# STM32F407.net
KiCad netlist of a schematic drawn in Altium Designer
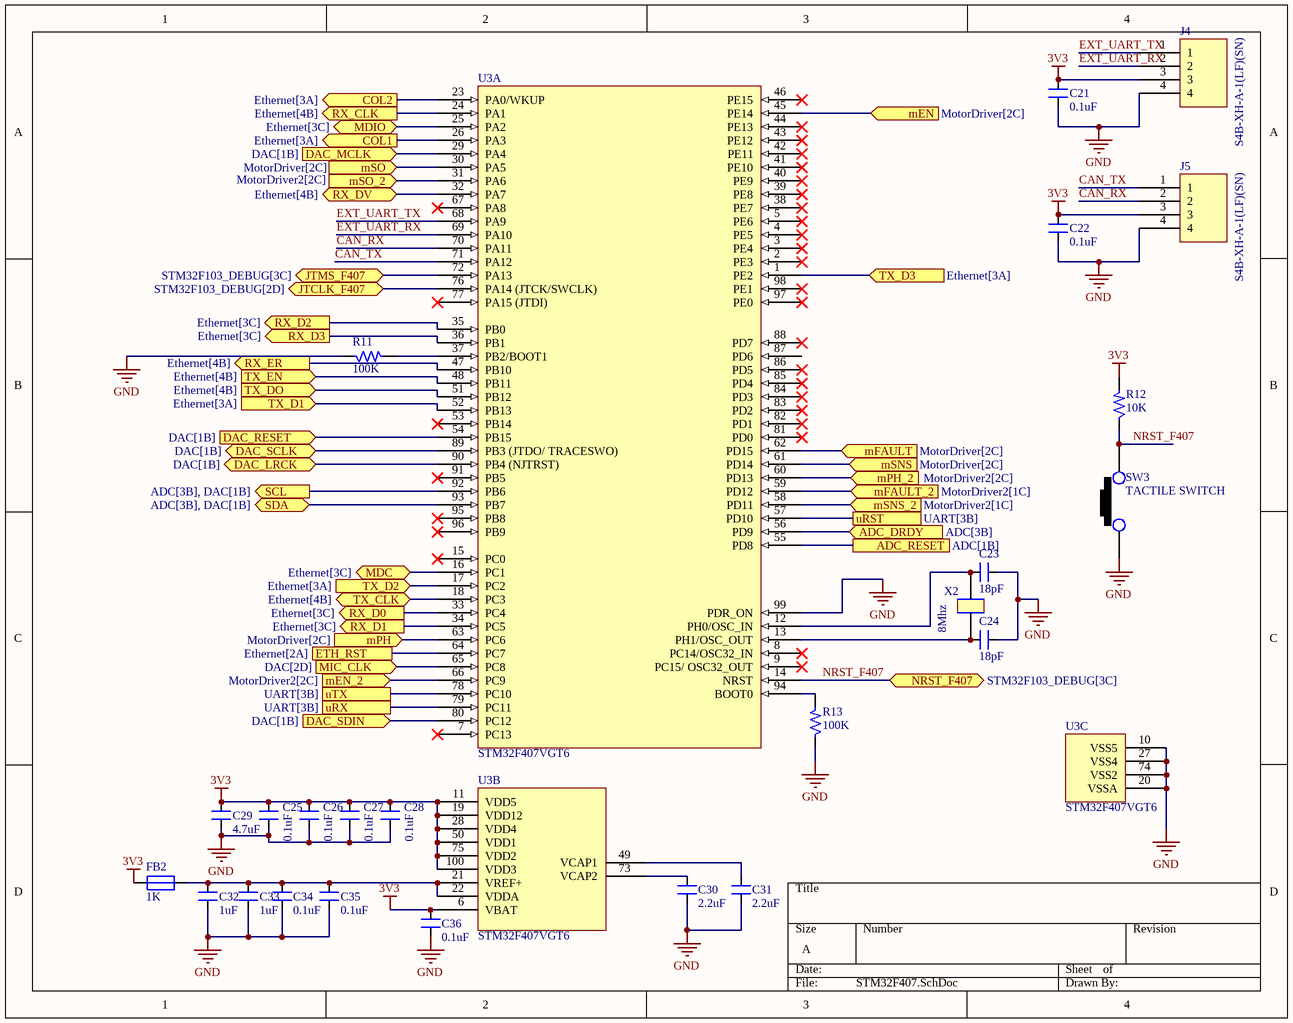
[diagram p0: STM32F407.SchDoc]

(export (version "E")
  (design (tool "Eeschema 10.0.6"))
  (components
    (comp (ref "C21")
      (value "0.1uF")
      (footprint "CAP_0805")
      (description "0.1µF ±5% 50V Ceramic Capacitor X7R 0805 (2012 Metric)")
      (fields
        (field (name "MANUFACTURER") "AVX Corporation")
        (field (name "MANUFACTURER PART NUMBER") "08055C104JAT4A")
      )
      (libsource (lib "ESTEEMPCBLIB") (part "CAP_0.1uF-50V-5%-0805"))
    )
    (comp (ref "C22")
      (value "0.1uF")
      (footprint "CAP_0805")
      (description "0.1µF ±5% 50V Ceramic Capacitor X7R 0805 (2012 Metric)")
      (fields
        (field (name "MANUFACTURER") "AVX Corporation")
        (field (name "MANUFACTURER PART NUMBER") "08055C104JAT4A")
      )
      (libsource (lib "ESTEEMPCBLIB") (part "CAP_0.1uF-50V-5%-0805"))
    )
    (comp (ref "C23")
      (value "18pF")
      (footprint "CAP_0805")
      (description "18pF ±5% 50V Ceramic Capacitor C0G, NP0 0805 (2012 Metric)")
      (fields
        (field (name "MANUFACTURER") "Yageo")
        (field (name "MANUFACTURER PART NUMBER") "CL21C180JBANNNC")
      )
      (libsource (lib "ESTEEMPCBLIB") (part "CAP_18pF-50V-5%-0805"))
    )
    (comp (ref "C24")
      (value "18pF")
      (footprint "CAP_0805")
      (description "18pF ±5% 50V Ceramic Capacitor C0G, NP0 0805 (2012 Metric)")
      (fields
        (field (name "MANUFACTURER") "Yageo")
        (field (name "MANUFACTURER PART NUMBER") "CL21C180JBANNNC")
      )
      (libsource (lib "ESTEEMPCBLIB") (part "CAP_18pF-50V-5%-0805"))
    )
    (comp (ref "C25")
      (value "0.1uF")
      (footprint "CAP_0805")
      (description "0.1µF ±5% 50V Ceramic Capacitor X7R 0805 (2012 Metric)")
      (fields
        (field (name "MANUFACTURER") "AVX Corporation")
        (field (name "MANUFACTURER PART NUMBER") "08055C104JAT4A")
      )
      (libsource (lib "ESTEEMPCBLIB") (part "CAP_0.1uF-50V-5%-0805"))
    )
    (comp (ref "C26")
      (value "0.1uF")
      (footprint "CAP_0805")
      (description "0.1µF ±5% 50V Ceramic Capacitor X7R 0805 (2012 Metric)")
      (fields
        (field (name "MANUFACTURER") "AVX Corporation")
        (field (name "MANUFACTURER PART NUMBER") "08055C104JAT4A")
      )
      (libsource (lib "ESTEEMPCBLIB") (part "CAP_0.1uF-50V-5%-0805"))
    )
    (comp (ref "C27")
      (value "0.1uF")
      (footprint "CAP_0805")
      (description "0.1µF ±5% 50V Ceramic Capacitor X7R 0805 (2012 Metric)")
      (fields
        (field (name "MANUFACTURER") "AVX Corporation")
        (field (name "MANUFACTURER PART NUMBER") "08055C104JAT4A")
      )
      (libsource (lib "ESTEEMPCBLIB") (part "CAP_0.1uF-50V-5%-0805"))
    )
    (comp (ref "C28")
      (value "0.1uF")
      (footprint "CAP_0805")
      (description "0.1µF ±5% 50V Ceramic Capacitor X7R 0805 (2012 Metric)")
      (fields
        (field (name "MANUFACTURER") "AVX Corporation")
        (field (name "MANUFACTURER PART NUMBER") "08055C104JAT4A")
      )
      (libsource (lib "ESTEEMPCBLIB") (part "CAP_0.1uF-50V-5%-0805"))
    )
    (comp (ref "C29")
      (value "4.7uF")
      (footprint "CAP_0805")
      (description "4.7µF ±10% 50V Ceramic Capacitor X5R 0805 (2012 Metric)")
      (fields
        (field (name "MANUFACTURER") "Yageo")
        (field (name "MANUFACTURER PART NUMBER") "GRM21BR61H475KE51L")
      )
      (libsource (lib "ESTEEMPCBLIB") (part "CAP_4.7uF-50V-10%-0805"))
    )
    (comp (ref "C30")
      (value "2.2uF")
      (footprint "CAP_0805")
      (description "2.2µF ±10% 25V Ceramic Capacitor X7R 0805 (2012 Metric)")
      (fields
        (field (name "MANUFACTURER") "KEMET")
        (field (name "MANUFACTURER PART NUMBER") "CL21B225KAFNFNE")
      )
      (libsource (lib "ESTEEMPCBLIB") (part "CAP_2.2uF-25V-10%-0805"))
    )
    (comp (ref "C31")
      (value "2.2uF")
      (footprint "CAP_0805")
      (description "2.2µF ±10% 25V Ceramic Capacitor X7R 0805 (2012 Metric)")
      (fields
        (field (name "MANUFACTURER") "KEMET")
        (field (name "MANUFACTURER PART NUMBER") "CL21B225KAFNFNE")
      )
      (libsource (lib "ESTEEMPCBLIB") (part "CAP_2.2uF-25V-10%-0805"))
    )
    (comp (ref "C32")
      (value "1uF")
      (footprint "CAP_0805")
      (description "1µF ±5% 50V Ceramic Capacitor X7R 0805 (2012 Metric)")
      (fields
        (field (name "MANUFACTURER") "Samsung")
        (field (name "MANUFACTURER PART NUMBER") "CC0805JKX7R9BB105")
      )
      (libsource (lib "ESTEEMPCBLIB") (part "CAP_1uF-50V-5%-0805"))
    )
    (comp (ref "C33")
      (value "1uF")
      (footprint "CAP_0805")
      (description "1µF ±5% 50V Ceramic Capacitor X7R 0805 (2012 Metric)")
      (fields
        (field (name "MANUFACTURER") "Samsung")
        (field (name "MANUFACTURER PART NUMBER") "CC0805JKX7R9BB105")
      )
      (libsource (lib "ESTEEMPCBLIB") (part "CAP_1uF-50V-5%-0805"))
    )
    (comp (ref "C34")
      (value "0.1uF")
      (footprint "CAP_0805")
      (description "0.1µF ±5% 50V Ceramic Capacitor X7R 0805 (2012 Metric)")
      (fields
        (field (name "MANUFACTURER") "AVX Corporation")
        (field (name "MANUFACTURER PART NUMBER") "08055C104JAT4A")
      )
      (libsource (lib "ESTEEMPCBLIB") (part "CAP_0.1uF-50V-5%-0805"))
    )
    (comp (ref "C35")
      (value "0.1uF")
      (footprint "CAP_0805")
      (description "0.1µF ±5% 50V Ceramic Capacitor X7R 0805 (2012 Metric)")
      (fields
        (field (name "MANUFACTURER") "AVX Corporation")
        (field (name "MANUFACTURER PART NUMBER") "08055C104JAT4A")
      )
      (libsource (lib "ESTEEMPCBLIB") (part "CAP_0.1uF-50V-5%-0805"))
    )
    (comp (ref "C36")
      (value "0.1uF")
      (footprint "CAP_0805")
      (description "0.1µF ±5% 50V Ceramic Capacitor X7R 0805 (2012 Metric)")
      (fields
        (field (name "MANUFACTURER") "AVX Corporation")
        (field (name "MANUFACTURER PART NUMBER") "08055C104JAT4A")
      )
      (libsource (lib "ESTEEMPCBLIB") (part "CAP_0.1uF-50V-5%-0805"))
    )
    (comp (ref "FB2")
      (value "1K")
      (footprint "IND_0805")
      (description "1 kOhms @ 100MHz 1 Power Line Ferrite Bead 0805 (2012 Metric) 1.6A")
      (fields
        (field (name "MANUFACTURER") "Laird")
        (field (name "MANUFACTURER PART NUMBER") "BLM21SP102SH1D")
      )
      (libsource (lib "ESTEEMPCBLIB") (part "FB_1K-100MHZ-1.6A-0805"))
    )
    (comp (ref "J4")
      (value "S4B-XH-A-1(LF)(SN)")
      (footprint "CON4_100_S4B-XH-A_TH_RA")
      (description "4 Pins, 1 Row 2.54mm Pitch, right angle Connector, male")
      (fields (field (name "MANUFACTURER") "Wurth Electronics") (field (name "MATING PART NUMBER") "XHP-4"))
      (libsource (lib "ESTEEMPCBLIB") (part "CON-PLG_4X1-100-RA-TH"))
    )
    (comp (ref "J5")
      (value "S4B-XH-A-1(LF)(SN)")
      (footprint "CON4_100_S4B-XH-A_TH_RA")
      (description "4 Pins, 1 Row 2.54mm Pitch, right angle Connector, male")
      (fields (field (name "MANUFACTURER") "Wurth Electronics") (field (name "MATING PART NUMBER") "XHP-4"))
      (libsource (lib "ESTEEMPCBLIB") (part "CON-PLG_4X1-100-RA-TH"))
    )
    (comp (ref "R11")
      (value "100K")
      (footprint "RES_0805")
      (description "100 kOhms ±1% 0.125W, 1/8W Chip Resistor 0805 (2012 Metric) Automotive AEC-Q200 Thick Film")
      (fields (field (name "MANUFACTURER") "Walsin") (field (name "MANUFACTURER PART NUMBER") "WR08X1003FTL"))
      (libsource (lib "ESTEEMPCBLIB") (part "RES_100K-0.125W-1%-0805"))
    )
    (comp (ref "R12")
      (value "10K")
      (footprint "RES_0603")
      (description "10 kOhms ±1% 0.1W, 1/10W Chip Resistor 0603 (1608 Metric) Automotive AEC-Q200 Thick Film")
      (fields (field (name "MANUFACTURER") "Walsin") (field (name "MANUFACTURER PART NUMBER") "WR06X1002FTL"))
      (libsource (lib "ESTEEMPCBLIB") (part "RES_10K-0.1W-1%-0603"))
    )
    (comp (ref "R13")
      (value "100K")
      (footprint "RES_0805")
      (description "100 kOhms ±1% 0.125W, 1/8W Chip Resistor 0805 (2012 Metric) Automotive AEC-Q200 Thick Film")
      (fields (field (name "MANUFACTURER") "Walsin") (field (name "MANUFACTURER PART NUMBER") "WR08X1003FTL"))
      (libsource (lib "ESTEEMPCBLIB") (part "RES_100K-0.125W-1%-0805"))
    )
    (comp (ref "SW3")
      (value "TACTILE SWITCH")
      (footprint "SW_342_SMD")
      (description "Tactile Switch SPST-NO Top Actuated Surface Mount")
      (fields
        (field (name "MANUFACTURER") "ITT C&K")
        (field (name "MANUFACTURER PART NUMBER") "RS-282G05A3-SMRT")
      )
      (libsource (lib "ESTEEMPCBLIB") (part "SW1_RS-282G05A3-SMRT-SMD"))
    )
    (comp (ref "U3")
      (value "STM32F407VGT6")
      (footprint "QFN100_19.6_669_58X10_SMD")
      (description "ARM® Cortex®-M4 STM32F4 Microcontroller IC 32-Bit 168MHz 1MB (1M x 8) FLASH 100-LQFP (14x14)")
      (fields (field (name "MANUFACTURER") "STMicroelectronics"))
      (libsource (lib "ESTEEMPCBLIB") (part "IC_STM32F407VGT6"))
    )
    (comp (ref "X2")
      (value "8Mhz")
      (footprint "XTAL_314_240X47_SMD")
      (description "8MHz ±30ppm Crystal 32pF 60 Ohms HC-49/US")
      (fields
        (field (name "MANUFACTURER") "Fox Electronics")
        (field (name "MANUFACTURER PART NUMBER") "ECS-80-32-5PX-TR")
      )
      (libsource (lib "ESTEEMPCBLIB") (part "XTAL_8MHZ-ECS-80-32-5PX-SMD"))
    )
  )
  (nets
    (net (code "1") (name "/ADC_DRDY") (class "Default")
      (node (ref "U3") (pin "56") (pinfunction "PD9_56") (pintype "input"))
    )
    (net (code "2") (name "/ADC_RESET") (class "Default")
      (node (ref "U3") (pin "55") (pinfunction "PD8_55") (pintype "input"))
    )
    (net (code "3") (name "/CAN_RX") (class "Default")
      (node (ref "J5") (pin "2") (pinfunction "2_2") (pintype "passive"))
      (node (ref "U3") (pin "70") (pinfunction "PA11_70") (pintype "input"))
    )
    (net (code "4") (name "/CAN_TX") (class "Default")
      (node (ref "J5") (pin "1") (pinfunction "1_1") (pintype "passive"))
      (node (ref "U3") (pin "71") (pinfunction "PA12_71") (pintype "input"))
    )
    (net (code "5") (name "/COL1") (class "Default")
      (node (ref "U3") (pin "26") (pinfunction "PA3_26") (pintype "input"))
    )
    (net (code "6") (name "/COL2") (class "Default")
      (node (ref "U3") (pin "23") (pinfunction "PA0/WKUP_23") (pintype "input"))
    )
    (net (code "7") (name "/DAC_LRCK") (class "Default")
      (node (ref "U3") (pin "90") (pinfunction "PB4_(NJTRST)_90") (pintype "input"))
    )
    (net (code "8") (name "/DAC_MCLK") (class "Default")
      (node (ref "U3") (pin "29") (pinfunction "PA4_29") (pintype "input"))
    )
    (net (code "9") (name "/DAC_RESET") (class "Default")
      (node (ref "U3") (pin "54") (pinfunction "PB15_54") (pintype "input"))
    )
    (net (code "10") (name "/DAC_SCLK") (class "Default")
      (node (ref "U3") (pin "89") (pinfunction "PB3_(JTDO/_TRACESWO)_89") (pintype "input"))
    )
    (net (code "11") (name "/DAC_SDIN") (class "Default")
      (node (ref "U3") (pin "80") (pinfunction "PC12_80") (pintype "input"))
    )
    (net (code "12") (name "/ETH_RST") (class "Default")
      (node (ref "U3") (pin "64") (pinfunction "PC7_64") (pintype "input"))
    )
    (net (code "13") (name "/EXT_UART_RX") (class "Default")
      (node (ref "J4") (pin "2") (pinfunction "2_2") (pintype "passive"))
      (node (ref "U3") (pin "69") (pinfunction "PA10_69") (pintype "input"))
    )
    (net (code "14") (name "/EXT_UART_TX") (class "Default")
      (node (ref "J4") (pin "1") (pinfunction "1_1") (pintype "passive"))
      (node (ref "U3") (pin "68") (pinfunction "PA9_68") (pintype "input"))
    )
    (net (code "15") (name "/JTCLK_F407") (class "Default")
      (node (ref "U3") (pin "76") (pinfunction "PA14_(JTCK/SWCLK)_76") (pintype "input"))
    )
    (net (code "16") (name "/JTMS_F407") (class "Default")
      (node (ref "U3") (pin "72") (pinfunction "PA13_72") (pintype "input"))
    )
    (net (code "17") (name "/MDC") (class "Default")
      (node (ref "U3") (pin "16") (pinfunction "PC1_16") (pintype "input"))
    )
    (net (code "18") (name "/MDIO") (class "Default")
      (node (ref "U3") (pin "25") (pinfunction "PA2_25") (pintype "input"))
    )
    (net (code "19") (name "/MIC_CLK") (class "Default")
      (node (ref "U3") (pin "65") (pinfunction "PC8_65") (pintype "input"))
    )
    (net (code "20") (name "/NRST_F407") (class "Default")
      (node (ref "R12") (pin "1") (pinfunction "1_1") (pintype "passive"))
      (node (ref "SW3") (pin "2") (pinfunction "2_2") (pintype "passive"))
      (node (ref "U3") (pin "14") (pinfunction "NRST_14") (pintype "input"))
    )
    (net (code "21") (name "/RX_CLK") (class "Default")
      (node (ref "U3") (pin "24") (pinfunction "PA1_24") (pintype "input"))
    )
    (net (code "22") (name "/RX_D0") (class "Default")
      (node (ref "U3") (pin "33") (pinfunction "PC4_33") (pintype "input"))
    )
    (net (code "23") (name "/RX_D1") (class "Default")
      (node (ref "U3") (pin "34") (pinfunction "PC5_34") (pintype "input"))
    )
    (net (code "24") (name "/RX_D2") (class "Default")
      (node (ref "U3") (pin "35") (pinfunction "PB0_35") (pintype "input"))
    )
    (net (code "25") (name "/RX_D3") (class "Default")
      (node (ref "U3") (pin "36") (pinfunction "PB1_36") (pintype "input"))
    )
    (net (code "26") (name "/RX_DV") (class "Default")
      (node (ref "U3") (pin "32") (pinfunction "PA7_32") (pintype "input"))
    )
    (net (code "27") (name "/RX_ER") (class "Default")
      (node (ref "U3") (pin "47") (pinfunction "PB10_47") (pintype "input"))
    )
    (net (code "28") (name "/SCL") (class "Default")
      (node (ref "U3") (pin "92") (pinfunction "PB6_92") (pintype "input"))
    )
    (net (code "29") (name "/SDA") (class "Default")
      (node (ref "U3") (pin "93") (pinfunction "PB7_93") (pintype "input"))
    )
    (net (code "30") (name "/TX_CLK") (class "Default")
      (node (ref "U3") (pin "18") (pinfunction "PC3_18") (pintype "input"))
    )
    (net (code "31") (name "/TX_D1") (class "Default")
      (node (ref "U3") (pin "52") (pinfunction "PB13_52") (pintype "input"))
    )
    (net (code "32") (name "/TX_D2") (class "Default")
      (node (ref "U3") (pin "17") (pinfunction "PC2_17") (pintype "input"))
    )
    (net (code "33") (name "/TX_D3") (class "Default")
      (node (ref "U3") (pin "1") (pinfunction "PE2_1") (pintype "input"))
    )
    (net (code "34") (name "/TX_DO") (class "Default")
      (node (ref "U3") (pin "51") (pinfunction "PB12_51") (pintype "input"))
    )
    (net (code "35") (name "/TX_EN") (class "Default")
      (node (ref "U3") (pin "48") (pinfunction "PB11_48") (pintype "input"))
    )
    (net (code "36") (name "/mEN") (class "Default")
      (node (ref "U3") (pin "45") (pinfunction "PE14_45") (pintype "input"))
    )
    (net (code "37") (name "/mEN_2") (class "Default")
      (node (ref "U3") (pin "66") (pinfunction "PC9_66") (pintype "input"))
    )
    (net (code "38") (name "/mFAULT") (class "Default")
      (node (ref "U3") (pin "62") (pinfunction "PD15_62") (pintype "input"))
    )
    (net (code "39") (name "/mFAULT_2") (class "Default")
      (node (ref "U3") (pin "59") (pinfunction "PD12_59") (pintype "input"))
    )
    (net (code "40") (name "/mPH") (class "Default")
      (node (ref "U3") (pin "63") (pinfunction "PC6_63") (pintype "input"))
    )
    (net (code "41") (name "/mPH_2") (class "Default")
      (node (ref "U3") (pin "60") (pinfunction "PD13_60") (pintype "input"))
    )
    (net (code "42") (name "/mSNS") (class "Default")
      (node (ref "U3") (pin "61") (pinfunction "PD14_61") (pintype "input"))
    )
    (net (code "43") (name "/mSNS_2") (class "Default")
      (node (ref "U3") (pin "58") (pinfunction "PD11_58") (pintype "input"))
    )
    (net (code "44") (name "/mSO") (class "Default")
      (node (ref "U3") (pin "30") (pinfunction "PA5_30") (pintype "input"))
    )
    (net (code "45") (name "/mSO_2") (class "Default")
      (node (ref "U3") (pin "31") (pinfunction "PA6_31") (pintype "input"))
    )
    (net (code "46") (name "/uRST") (class "Default")
      (node (ref "U3") (pin "57") (pinfunction "PD10_57") (pintype "input"))
    )
    (net (code "47") (name "/uRX") (class "Default")
      (node (ref "U3") (pin "79") (pinfunction "PC11_79") (pintype "input"))
    )
    (net (code "48") (name "/uTX") (class "Default")
      (node (ref "U3") (pin "78") (pinfunction "PC10_78") (pintype "input"))
    )
    (net (code "49") (name "3V3") (class "Default")
      (node (ref "C21") (pin "2") (pinfunction "2_2") (pintype "passive"))
      (node (ref "C22") (pin "2") (pinfunction "2_2") (pintype "passive"))
      (node (ref "C25") (pin "2") (pinfunction "2_2") (pintype "passive"))
      (node (ref "C26") (pin "2") (pinfunction "2_2") (pintype "passive"))
      (node (ref "C27") (pin "2") (pinfunction "2_2") (pintype "passive"))
      (node (ref "C28") (pin "2") (pinfunction "2_2") (pintype "passive"))
      (node (ref "C29") (pin "1") (pinfunction "1_1") (pintype "passive"))
      (node (ref "C36") (pin "2") (pinfunction "2_2") (pintype "passive"))
      (node (ref "FB2") (pin "1") (pinfunction "1_1") (pintype "passive"))
      (node (ref "J4") (pin "3") (pinfunction "3_3") (pintype "passive"))
      (node (ref "J5") (pin "3") (pinfunction "3_3") (pintype "passive"))
      (node (ref "R12") (pin "2") (pinfunction "2_2") (pintype "passive"))
      (node (ref "U3") (pin "100") (pinfunction "VDD3_100") (pintype "passive"))
      (node (ref "U3") (pin "11") (pinfunction "VDD5_11") (pintype "passive"))
      (node (ref "U3") (pin "19") (pinfunction "VDD12_19") (pintype "passive"))
      (node (ref "U3") (pin "28") (pinfunction "VDD4_28") (pintype "passive"))
      (node (ref "U3") (pin "50") (pinfunction "VDD1_50") (pintype "passive"))
      (node (ref "U3") (pin "6") (pinfunction "VBAT_6") (pintype "passive"))
      (node (ref "U3") (pin "75") (pinfunction "VDD2_75") (pintype "passive"))
    )
    (net (code "50") (name "GND") (class "Default")
      (node (ref "C21") (pin "1") (pinfunction "1_1") (pintype "passive"))
      (node (ref "C22") (pin "1") (pinfunction "1_1") (pintype "passive"))
      (node (ref "C23") (pin "2") (pinfunction "2_2") (pintype "passive"))
      (node (ref "C24") (pin "2") (pinfunction "2_2") (pintype "passive"))
      (node (ref "C25") (pin "1") (pinfunction "1_1") (pintype "passive"))
      (node (ref "C26") (pin "1") (pinfunction "1_1") (pintype "passive"))
      (node (ref "C27") (pin "1") (pinfunction "1_1") (pintype "passive"))
      (node (ref "C28") (pin "1") (pinfunction "1_1") (pintype "passive"))
      (node (ref "C29") (pin "2") (pinfunction "2_2") (pintype "passive"))
      (node (ref "C30") (pin "2") (pinfunction "2_2") (pintype "passive"))
      (node (ref "C31") (pin "1") (pinfunction "1_1") (pintype "passive"))
      (node (ref "C32") (pin "1") (pinfunction "1_1") (pintype "passive"))
      (node (ref "C33") (pin "1") (pinfunction "1_1") (pintype "passive"))
      (node (ref "C34") (pin "1") (pinfunction "1_1") (pintype "passive"))
      (node (ref "C35") (pin "1") (pinfunction "1_1") (pintype "passive"))
      (node (ref "C36") (pin "1") (pinfunction "1_1") (pintype "passive"))
      (node (ref "J4") (pin "4") (pinfunction "4_4") (pintype "passive"))
      (node (ref "J5") (pin "4") (pinfunction "4_4") (pintype "passive"))
      (node (ref "R11") (pin "1") (pinfunction "1_1") (pintype "passive"))
      (node (ref "R13") (pin "1") (pinfunction "1_1") (pintype "passive"))
      (node (ref "SW3") (pin "1") (pinfunction "1_1") (pintype "passive"))
      (node (ref "U3") (pin "10") (pinfunction "VSS5_10") (pintype "passive"))
      (node (ref "U3") (pin "20") (pinfunction "VSSA_20") (pintype "passive"))
      (node (ref "U3") (pin "27") (pinfunction "VSS4_27") (pintype "passive"))
      (node (ref "U3") (pin "74") (pinfunction "VSS2_74") (pintype "passive"))
      (node (ref "U3") (pin "99") (pinfunction "PDR_ON_99") (pintype "input"))
    )
    (net (code "51") (name "Net-(U3A-BOOT0)") (class "Default")
      (node (ref "R13") (pin "2") (pinfunction "2_2") (pintype "passive"))
      (node (ref "U3") (pin "94") (pinfunction "BOOT0_94") (pintype "input"))
    )
    (net (code "52") (name "Net-(U3A-PB2{slash}BOOT1)") (class "Default")
      (node (ref "R11") (pin "2") (pinfunction "2_2") (pintype "passive"))
      (node (ref "U3") (pin "37") (pinfunction "PB2/BOOT1_37") (pintype "input"))
    )
    (net (code "53") (name "Net-(U3A-PH0{slash}OSC_IN)") (class "Default")
      (node (ref "C23") (pin "1") (pinfunction "1_1") (pintype "passive"))
      (node (ref "U3") (pin "12") (pinfunction "PH0/OSC_IN_12") (pintype "input"))
      (node (ref "X2") (pin "2") (pinfunction "2_2") (pintype "passive"))
    )
    (net (code "54") (name "Net-(U3A-PH1{slash}OSC_OUT)") (class "Default")
      (node (ref "C24") (pin "1") (pinfunction "1_1") (pintype "passive"))
      (node (ref "U3") (pin "13") (pinfunction "PH1/OSC_OUT_13") (pintype "input"))
      (node (ref "X2") (pin "1") (pinfunction "1_1") (pintype "passive"))
    )
    (net (code "55") (name "Net-(U3B-VCAP1)") (class "Default")
      (node (ref "C31") (pin "2") (pinfunction "2_2") (pintype "passive"))
      (node (ref "U3") (pin "49") (pinfunction "VCAP1_49") (pintype "passive"))
    )
    (net (code "56") (name "Net-(U3B-VCAP2)") (class "Default")
      (node (ref "C30") (pin "1") (pinfunction "1_1") (pintype "passive"))
      (node (ref "U3") (pin "73") (pinfunction "VCAP2_73") (pintype "passive"))
    )
    (net (code "57") (name "Net-(U3B-VDDA)") (class "Default")
      (node (ref "C32") (pin "2") (pinfunction "2_2") (pintype "passive"))
      (node (ref "C33") (pin "2") (pinfunction "2_2") (pintype "passive"))
      (node (ref "C34") (pin "2") (pinfunction "2_2") (pintype "passive"))
      (node (ref "C35") (pin "2") (pinfunction "2_2") (pintype "passive"))
      (node (ref "FB2") (pin "2") (pinfunction "2_2") (pintype "passive"))
      (node (ref "U3") (pin "21") (pinfunction "VREF+_21") (pintype "passive"))
      (node (ref "U3") (pin "22") (pinfunction "VDDA_22") (pintype "passive"))
    )
    (net (code "58") (name "unconnected-(U3A-PA8-Pad67)") (class "Default")
      (node (ref "U3") (pin "67") (pinfunction "PA8_67") (pintype "input+no_connect"))
    )
    (net (code "59") (name "unconnected-(U3A-PA15_(JTDI)-Pad77)") (class "Default")
      (node (ref "U3") (pin "77") (pinfunction "PA15_(JTDI)_77") (pintype "input+no_connect"))
    )
    (net (code "60") (name "unconnected-(U3A-PB5-Pad91)") (class "Default")
      (node (ref "U3") (pin "91") (pinfunction "PB5_91") (pintype "input+no_connect"))
    )
    (net (code "61") (name "unconnected-(U3A-PB8-Pad95)") (class "Default")
      (node (ref "U3") (pin "95") (pinfunction "PB8_95") (pintype "input+no_connect"))
    )
    (net (code "62") (name "unconnected-(U3A-PB9-Pad96)") (class "Default")
      (node (ref "U3") (pin "96") (pinfunction "PB9_96") (pintype "input+no_connect"))
    )
    (net (code "63") (name "unconnected-(U3A-PB14-Pad53)") (class "Default")
      (node (ref "U3") (pin "53") (pinfunction "PB14_53") (pintype "input+no_connect"))
    )
    (net (code "64") (name "unconnected-(U3A-PC0-Pad15)") (class "Default")
      (node (ref "U3") (pin "15") (pinfunction "PC0_15") (pintype "input+no_connect"))
    )
    (net (code "65") (name "unconnected-(U3A-PC13-Pad7)") (class "Default")
      (node (ref "U3") (pin "7") (pinfunction "PC13_7") (pintype "input+no_connect"))
    )
    (net (code "66") (name "unconnected-(U3A-PC14{slash}OSC32_IN-Pad8)") (class "Default")
      (node (ref "U3") (pin "8") (pinfunction "PC14/OSC32_IN_8") (pintype "input+no_connect"))
    )
    (net (code "67") (name "unconnected-(U3A-PC15{slash}_OSC32_OUT-Pad9)") (class "Default")
      (node (ref "U3") (pin "9") (pinfunction "PC15/_OSC32_OUT_9") (pintype "input+no_connect"))
    )
    (net (code "68") (name "unconnected-(U3A-PD0-Pad81)") (class "Default")
      (node (ref "U3") (pin "81") (pinfunction "PD0_81") (pintype "input+no_connect"))
    )
    (net (code "69") (name "unconnected-(U3A-PD1-Pad82)") (class "Default")
      (node (ref "U3") (pin "82") (pinfunction "PD1_82") (pintype "input+no_connect"))
    )
    (net (code "70") (name "unconnected-(U3A-PD2-Pad83)") (class "Default")
      (node (ref "U3") (pin "83") (pinfunction "PD2_83") (pintype "input+no_connect"))
    )
    (net (code "71") (name "unconnected-(U3A-PD3-Pad84)") (class "Default")
      (node (ref "U3") (pin "84") (pinfunction "PD3_84") (pintype "input+no_connect"))
    )
    (net (code "72") (name "unconnected-(U3A-PD4-Pad85)") (class "Default")
      (node (ref "U3") (pin "85") (pinfunction "PD4_85") (pintype "input+no_connect"))
    )
    (net (code "73") (name "unconnected-(U3A-PD5-Pad86)") (class "Default")
      (node (ref "U3") (pin "86") (pinfunction "PD5_86") (pintype "input+no_connect"))
    )
    (net (code "74") (name "unconnected-(U3A-PD6-Pad87)") (class "Default")
      (node (ref "U3") (pin "87") (pinfunction "PD6_87") (pintype "input"))
    )
    (net (code "75") (name "unconnected-(U3A-PD7-Pad88)") (class "Default")
      (node (ref "U3") (pin "88") (pinfunction "PD7_88") (pintype "input+no_connect"))
    )
    (net (code "76") (name "unconnected-(U3A-PE0-Pad97)") (class "Default")
      (node (ref "U3") (pin "97") (pinfunction "PE0_97") (pintype "input+no_connect"))
    )
    (net (code "77") (name "unconnected-(U3A-PE1-Pad98)") (class "Default")
      (node (ref "U3") (pin "98") (pinfunction "PE1_98") (pintype "input+no_connect"))
    )
    (net (code "78") (name "unconnected-(U3A-PE3-Pad2)") (class "Default")
      (node (ref "U3") (pin "2") (pinfunction "PE3_2") (pintype "input+no_connect"))
    )
    (net (code "79") (name "unconnected-(U3A-PE4-Pad3)") (class "Default")
      (node (ref "U3") (pin "3") (pinfunction "PE4_3") (pintype "input+no_connect"))
    )
    (net (code "80") (name "unconnected-(U3A-PE5-Pad4)") (class "Default")
      (node (ref "U3") (pin "4") (pinfunction "PE5_4") (pintype "input+no_connect"))
    )
    (net (code "81") (name "unconnected-(U3A-PE6-Pad5)") (class "Default")
      (node (ref "U3") (pin "5") (pinfunction "PE6_5") (pintype "input+no_connect"))
    )
    (net (code "82") (name "unconnected-(U3A-PE7-Pad38)") (class "Default")
      (node (ref "U3") (pin "38") (pinfunction "PE7_38") (pintype "input+no_connect"))
    )
    (net (code "83") (name "unconnected-(U3A-PE8-Pad39)") (class "Default")
      (node (ref "U3") (pin "39") (pinfunction "PE8_39") (pintype "input+no_connect"))
    )
    (net (code "84") (name "unconnected-(U3A-PE9-Pad40)") (class "Default")
      (node (ref "U3") (pin "40") (pinfunction "PE9_40") (pintype "input+no_connect"))
    )
    (net (code "85") (name "unconnected-(U3A-PE10-Pad41)") (class "Default")
      (node (ref "U3") (pin "41") (pinfunction "PE10_41") (pintype "input+no_connect"))
    )
    (net (code "86") (name "unconnected-(U3A-PE11-Pad42)") (class "Default")
      (node (ref "U3") (pin "42") (pinfunction "PE11_42") (pintype "input+no_connect"))
    )
    (net (code "87") (name "unconnected-(U3A-PE12-Pad43)") (class "Default")
      (node (ref "U3") (pin "43") (pinfunction "PE12_43") (pintype "input+no_connect"))
    )
    (net (code "88") (name "unconnected-(U3A-PE13-Pad44)") (class "Default")
      (node (ref "U3") (pin "44") (pinfunction "PE13_44") (pintype "input+no_connect"))
    )
    (net (code "89") (name "unconnected-(U3A-PE15-Pad46)") (class "Default")
      (node (ref "U3") (pin "46") (pinfunction "PE15_46") (pintype "input+no_connect"))
    )
  )
)
